# HalfBridge_V01.net
KiCad netlist of a schematic drawn in Altium Designer
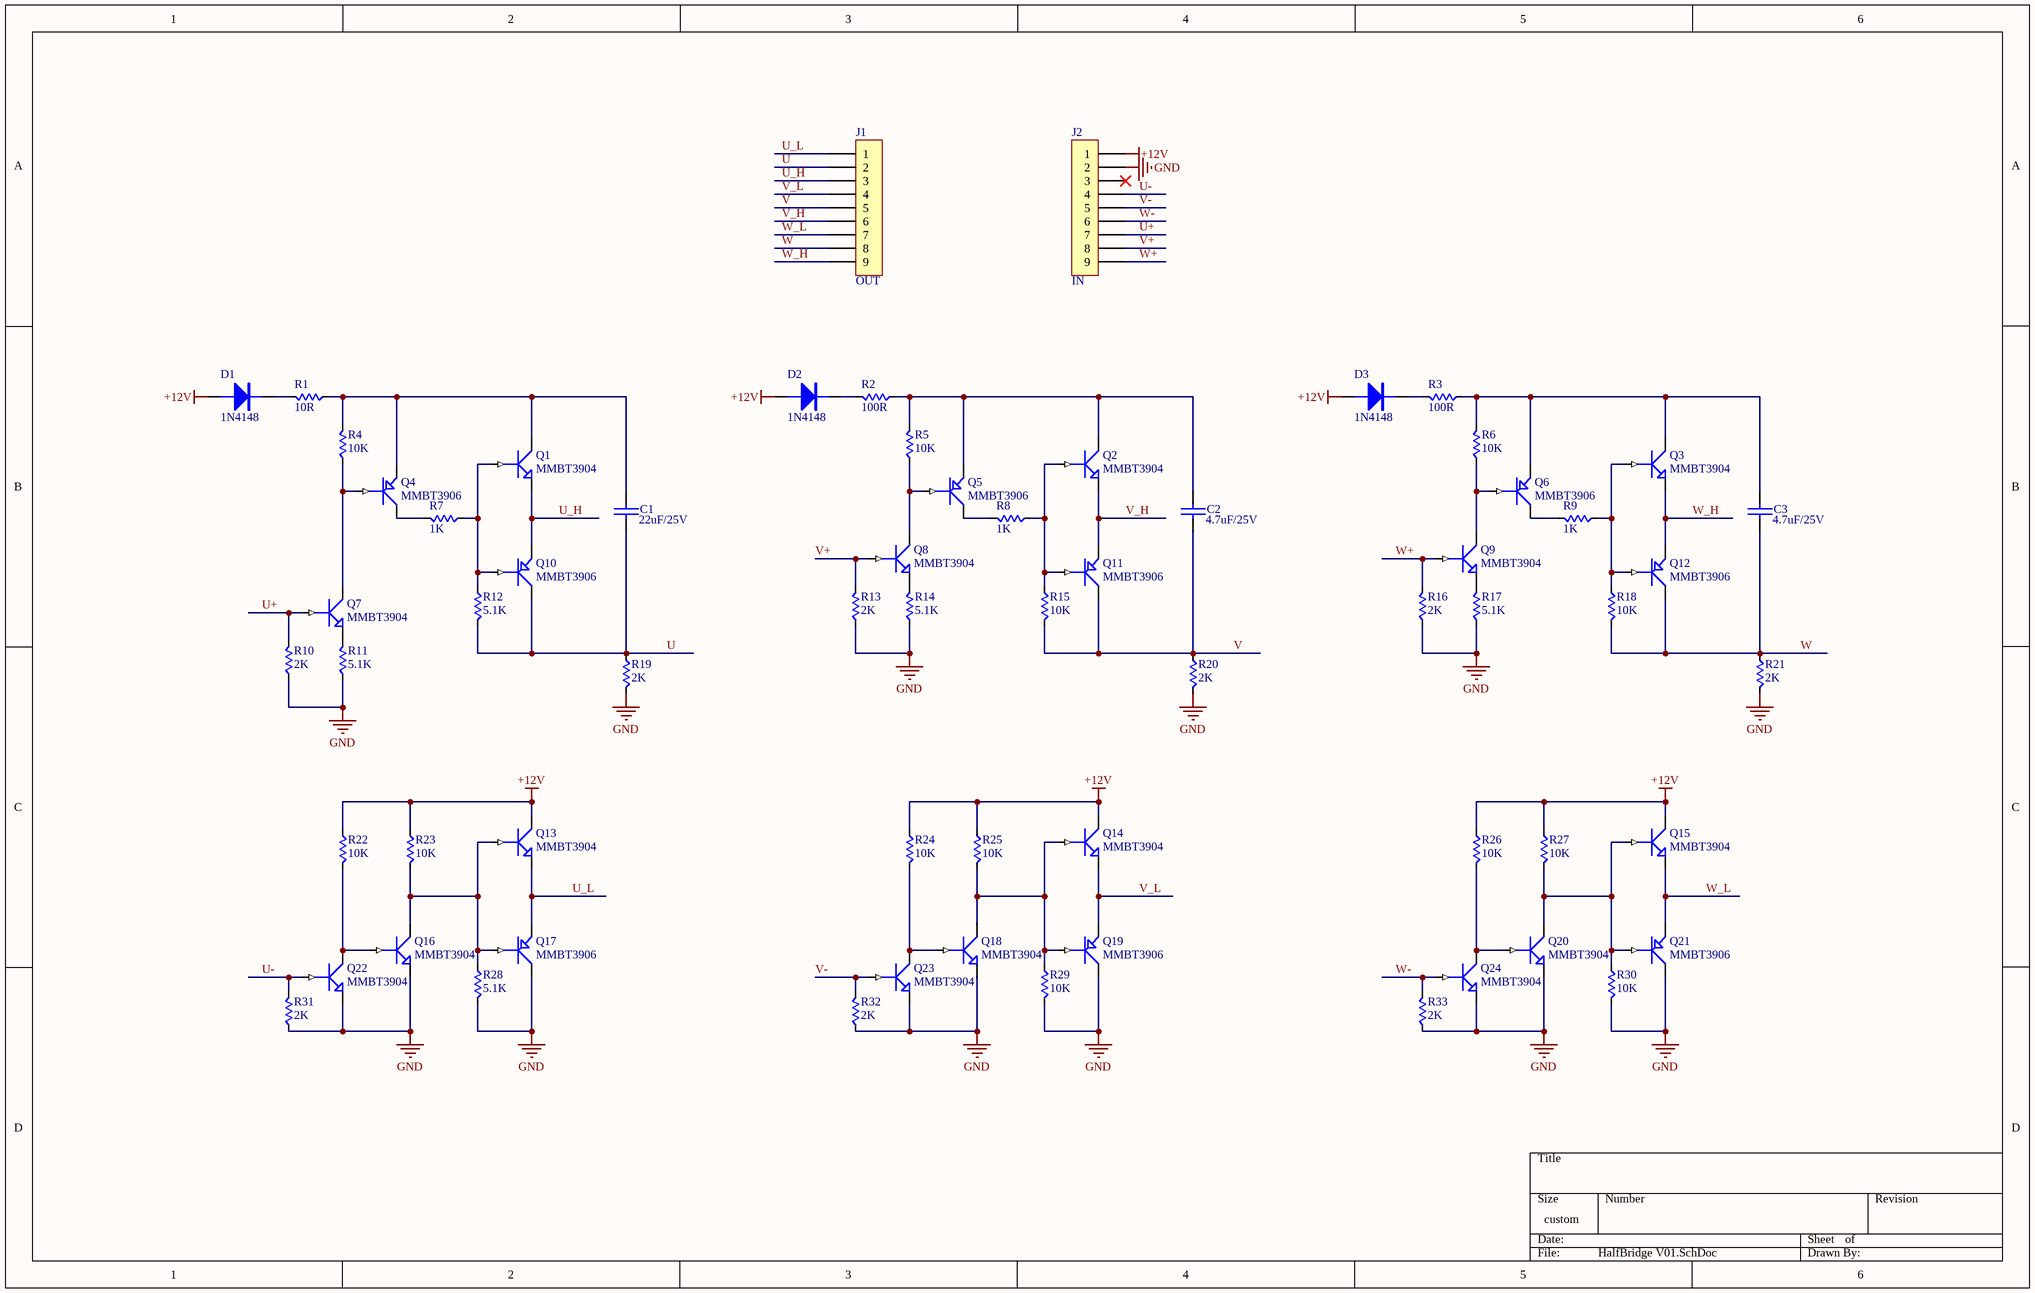
[diagram p0: HalfBridge V01.SchDoc]

(export (version "E")
  (design (tool "Eeschema 10.0.6"))
  (components
    (comp (ref "C1")
      (value "22uF/25V")
      (footprint "0805C")
      (description "Capacitor")
      (libsource (lib "*") (part "CAP"))
    )
    (comp (ref "C2")
      (value "4.7uF/25V")
      (footprint "0805C")
      (description "Capacitor")
      (libsource (lib "*") (part "CAP"))
    )
    (comp (ref "C3")
      (value "4.7uF/25V")
      (footprint "0805C")
      (description "Capacitor")
      (libsource (lib "*") (part "CAP"))
    )
    (comp (ref "D1")
      (value "1N4148")
      (footprint "SOD-123")
      (description "Diode")
      (libsource (lib "*") (part "DIODE1"))
    )
    (comp (ref "D2")
      (value "1N4148")
      (footprint "SOD-123")
      (description "Diode")
      (libsource (lib "*") (part "DIODE1"))
    )
    (comp (ref "D3")
      (value "1N4148")
      (footprint "SOD-123")
      (description "Diode")
      (libsource (lib "*") (part "DIODE1"))
    )
    (comp (ref "J1")
      (value "OUT")
      (footprint "SMT2.54-1X9-F")
      (description "Connector")
      (libsource (lib "") (part "CON9_1"))
    )
    (comp (ref "J2")
      (value "IN")
      (footprint "SMT2.54-1X9-F")
      (description "Connector")
      (libsource (lib "COFLY-SCH") (part "CON9"))
    )
    (comp (ref "Q1")
      (value "MMBT3904")
      (footprint "SOT-23S")
      (description "NPN Transistor")
      (libsource (lib "COFLY-SCH") (part "NPN1"))
    )
    (comp (ref "Q2")
      (value "MMBT3904")
      (footprint "SOT-23S")
      (description "NPN Transistor")
      (libsource (lib "COFLY-SCH") (part "NPN1"))
    )
    (comp (ref "Q3")
      (value "MMBT3904")
      (footprint "SOT-23S")
      (description "NPN Transistor")
      (libsource (lib "COFLY-SCH") (part "NPN1"))
    )
    (comp (ref "Q4")
      (value "MMBT3906")
      (footprint "SOT-23S")
      (description "PNP Transistor")
      (libsource (lib "COFLY-SCH") (part "PNP1"))
    )
    (comp (ref "Q5")
      (value "MMBT3906")
      (footprint "SOT-23S")
      (description "PNP Transistor")
      (libsource (lib "COFLY-SCH") (part "PNP1"))
    )
    (comp (ref "Q6")
      (value "MMBT3906")
      (footprint "SOT-23S")
      (description "PNP Transistor")
      (libsource (lib "COFLY-SCH") (part "PNP1"))
    )
    (comp (ref "Q7")
      (value "MMBT3904")
      (footprint "SOT-23S")
      (description "NPN Transistor")
      (libsource (lib "COFLY-SCH") (part "NPN1"))
    )
    (comp (ref "Q8")
      (value "MMBT3904")
      (footprint "SOT-23S")
      (description "NPN Transistor")
      (libsource (lib "COFLY-SCH") (part "NPN1"))
    )
    (comp (ref "Q9")
      (value "MMBT3904")
      (footprint "SOT-23S")
      (description "NPN Transistor")
      (libsource (lib "COFLY-SCH") (part "NPN1"))
    )
    (comp (ref "Q10")
      (value "MMBT3906")
      (footprint "SOT-23S")
      (description "PNP Transistor")
      (libsource (lib "COFLY-SCH") (part "PNP1"))
    )
    (comp (ref "Q11")
      (value "MMBT3906")
      (footprint "SOT-23S")
      (description "PNP Transistor")
      (libsource (lib "COFLY-SCH") (part "PNP1"))
    )
    (comp (ref "Q12")
      (value "MMBT3906")
      (footprint "SOT-23S")
      (description "PNP Transistor")
      (libsource (lib "COFLY-SCH") (part "PNP1"))
    )
    (comp (ref "Q13")
      (value "MMBT3904")
      (footprint "SOT-23S")
      (description "NPN Transistor")
      (libsource (lib "COFLY-SCH") (part "NPN1"))
    )
    (comp (ref "Q14")
      (value "MMBT3904")
      (footprint "SOT-23S")
      (description "NPN Transistor")
      (libsource (lib "COFLY-SCH") (part "NPN1"))
    )
    (comp (ref "Q15")
      (value "MMBT3904")
      (footprint "SOT-23S")
      (description "NPN Transistor")
      (libsource (lib "COFLY-SCH") (part "NPN1"))
    )
    (comp (ref "Q16")
      (value "MMBT3904")
      (footprint "SOT-23S")
      (description "NPN Transistor")
      (libsource (lib "COFLY-SCH") (part "NPN1"))
    )
    (comp (ref "Q17")
      (value "MMBT3906")
      (footprint "SOT-23S")
      (description "PNP Transistor")
      (libsource (lib "COFLY-SCH") (part "PNP1"))
    )
    (comp (ref "Q18")
      (value "MMBT3904")
      (footprint "SOT-23S")
      (description "NPN Transistor")
      (libsource (lib "COFLY-SCH") (part "NPN1"))
    )
    (comp (ref "Q19")
      (value "MMBT3906")
      (footprint "SOT-23S")
      (description "PNP Transistor")
      (libsource (lib "COFLY-SCH") (part "PNP1"))
    )
    (comp (ref "Q20")
      (value "MMBT3904")
      (footprint "SOT-23S")
      (description "NPN Transistor")
      (libsource (lib "COFLY-SCH") (part "NPN1"))
    )
    (comp (ref "Q21")
      (value "MMBT3906")
      (footprint "SOT-23S")
      (description "PNP Transistor")
      (libsource (lib "COFLY-SCH") (part "PNP1"))
    )
    (comp (ref "Q22")
      (value "MMBT3904")
      (footprint "SOT-23S")
      (description "NPN Transistor")
      (libsource (lib "COFLY-SCH") (part "NPN1"))
    )
    (comp (ref "Q23")
      (value "MMBT3904")
      (footprint "SOT-23S")
      (description "NPN Transistor")
      (libsource (lib "COFLY-SCH") (part "NPN1"))
    )
    (comp (ref "Q24")
      (value "MMBT3904")
      (footprint "SOT-23S")
      (description "NPN Transistor")
      (libsource (lib "COFLY-SCH") (part "NPN1"))
    )
    (comp (ref "R1") (value "10R") (footprint "0603R") (libsource (lib "COFLY-SCH") (part "RES")))
    (comp (ref "R2") (value "100R") (footprint "0603R") (libsource (lib "COFLY-SCH") (part "RES")))
    (comp (ref "R3") (value "100R") (footprint "0603R") (libsource (lib "COFLY-SCH") (part "RES")))
    (comp (ref "R4") (value "10K") (footprint "0603R") (libsource (lib "COFLY-SCH") (part "RES")))
    (comp (ref "R5") (value "10K") (footprint "0603R") (libsource (lib "COFLY-SCH") (part "RES")))
    (comp (ref "R6") (value "10K") (footprint "0603R") (libsource (lib "COFLY-SCH") (part "RES")))
    (comp (ref "R7") (value "1K") (footprint "0603R") (libsource (lib "COFLY-SCH") (part "RES")))
    (comp (ref "R8") (value "1K") (footprint "0603R") (libsource (lib "COFLY-SCH") (part "RES")))
    (comp (ref "R9") (value "1K") (footprint "0603R") (libsource (lib "COFLY-SCH") (part "RES")))
    (comp (ref "R10") (value "2K") (footprint "0603R") (libsource (lib "COFLY-SCH") (part "RES")))
    (comp (ref "R11") (value "5.1K") (footprint "0603R") (libsource (lib "COFLY-SCH") (part "RES")))
    (comp (ref "R12") (value "5.1K") (footprint "0603R") (libsource (lib "COFLY-SCH") (part "RES")))
    (comp (ref "R13") (value "2K") (footprint "0603R") (libsource (lib "COFLY-SCH") (part "RES")))
    (comp (ref "R14") (value "5.1K") (footprint "0603R") (libsource (lib "COFLY-SCH") (part "RES")))
    (comp (ref "R15") (value "10K") (footprint "0603R") (libsource (lib "COFLY-SCH") (part "RES")))
    (comp (ref "R16") (value "2K") (footprint "0603R") (libsource (lib "COFLY-SCH") (part "RES")))
    (comp (ref "R17") (value "5.1K") (footprint "0603R") (libsource (lib "COFLY-SCH") (part "RES")))
    (comp (ref "R18") (value "10K") (footprint "0603R") (libsource (lib "COFLY-SCH") (part "RES")))
    (comp (ref "R19") (value "2K") (footprint "0603R") (libsource (lib "COFLY-SCH") (part "RES")))
    (comp (ref "R20") (value "2K") (footprint "0603R") (libsource (lib "COFLY-SCH") (part "RES")))
    (comp (ref "R21") (value "2K") (footprint "0603R") (libsource (lib "COFLY-SCH") (part "RES")))
    (comp (ref "R22") (value "10K") (footprint "0603R") (libsource (lib "COFLY-SCH") (part "RES")))
    (comp (ref "R23") (value "10K") (footprint "0603R") (libsource (lib "COFLY-SCH") (part "RES")))
    (comp (ref "R24") (value "10K") (footprint "0603R") (libsource (lib "COFLY-SCH") (part "RES")))
    (comp (ref "R25") (value "10K") (footprint "0603R") (libsource (lib "COFLY-SCH") (part "RES")))
    (comp (ref "R26") (value "10K") (footprint "0603R") (libsource (lib "COFLY-SCH") (part "RES")))
    (comp (ref "R27") (value "10K") (footprint "0603R") (libsource (lib "COFLY-SCH") (part "RES")))
    (comp (ref "R28") (value "5.1K") (footprint "0603R") (libsource (lib "COFLY-SCH") (part "RES")))
    (comp (ref "R29") (value "10K") (footprint "0603R") (libsource (lib "COFLY-SCH") (part "RES")))
    (comp (ref "R30") (value "10K") (footprint "0603R") (libsource (lib "COFLY-SCH") (part "RES")))
    (comp (ref "R31") (value "2K") (footprint "0603R") (libsource (lib "COFLY-SCH") (part "RES")))
    (comp (ref "R32") (value "2K") (footprint "0603R") (libsource (lib "COFLY-SCH") (part "RES")))
    (comp (ref "R33") (value "2K") (footprint "0603R") (libsource (lib "COFLY-SCH") (part "RES")))
  )
  (nets
    (net (code "1") (name "+12V") (class "Default")
      (node (ref "D1") (pin "1") (pinfunction "1_1") (pintype "passive"))
      (node (ref "D2") (pin "1") (pinfunction "1_1") (pintype "passive"))
      (node (ref "D3") (pin "1") (pinfunction "1_1") (pintype "passive"))
      (node (ref "J2") (pin "1") (pinfunction "1_1") (pintype "passive"))
      (node (ref "Q13") (pin "3") (pinfunction "C_3") (pintype "passive"))
      (node (ref "Q14") (pin "3") (pinfunction "C_3") (pintype "passive"))
      (node (ref "Q15") (pin "3") (pinfunction "C_3") (pintype "passive"))
      (node (ref "R22") (pin "1") (pinfunction "1_1") (pintype "passive"))
      (node (ref "R23") (pin "1") (pinfunction "1_1") (pintype "passive"))
      (node (ref "R24") (pin "1") (pinfunction "1_1") (pintype "passive"))
      (node (ref "R25") (pin "1") (pinfunction "1_1") (pintype "passive"))
      (node (ref "R26") (pin "1") (pinfunction "1_1") (pintype "passive"))
      (node (ref "R27") (pin "1") (pinfunction "1_1") (pintype "passive"))
    )
    (net (code "2") (name "/U") (class "Default")
      (node (ref "C1") (pin "2") (pinfunction "2_2") (pintype "passive"))
      (node (ref "J1") (pin "2") (pinfunction "2_2") (pintype "passive"))
      (node (ref "Q10") (pin "3") (pinfunction "C_3") (pintype "passive"))
      (node (ref "R12") (pin "2") (pinfunction "2_2") (pintype "passive"))
      (node (ref "R19") (pin "2") (pinfunction "2_2") (pintype "passive"))
    )
    (net (code "3") (name "/U+") (class "Default")
      (node (ref "J2") (pin "7") (pinfunction "7_7") (pintype "passive"))
      (node (ref "Q7") (pin "1") (pinfunction "B_1") (pintype "input"))
      (node (ref "R10") (pin "2") (pinfunction "2_2") (pintype "passive"))
    )
    (net (code "4") (name "/U-") (class "Default")
      (node (ref "J2") (pin "4") (pinfunction "4_4") (pintype "passive"))
      (node (ref "Q22") (pin "1") (pinfunction "B_1") (pintype "input"))
      (node (ref "R31") (pin "2") (pinfunction "2_2") (pintype "passive"))
    )
    (net (code "5") (name "/U_H") (class "Default")
      (node (ref "J1") (pin "3") (pinfunction "3_3") (pintype "passive"))
      (node (ref "Q1") (pin "2") (pinfunction "E_2") (pintype "passive"))
      (node (ref "Q10") (pin "2") (pinfunction "E_2") (pintype "passive"))
    )
    (net (code "6") (name "/U_L") (class "Default")
      (node (ref "J1") (pin "1") (pinfunction "1_1") (pintype "passive"))
      (node (ref "Q13") (pin "2") (pinfunction "E_2") (pintype "passive"))
      (node (ref "Q17") (pin "2") (pinfunction "E_2") (pintype "passive"))
    )
    (net (code "7") (name "/V") (class "Default")
      (node (ref "C2") (pin "2") (pinfunction "2_2") (pintype "passive"))
      (node (ref "J1") (pin "5") (pinfunction "5_5") (pintype "passive"))
      (node (ref "Q11") (pin "3") (pinfunction "C_3") (pintype "passive"))
      (node (ref "R15") (pin "2") (pinfunction "2_2") (pintype "passive"))
      (node (ref "R20") (pin "2") (pinfunction "2_2") (pintype "passive"))
    )
    (net (code "8") (name "/V+") (class "Default")
      (node (ref "J2") (pin "8") (pinfunction "8_8") (pintype "passive"))
      (node (ref "Q8") (pin "1") (pinfunction "B_1") (pintype "input"))
      (node (ref "R13") (pin "2") (pinfunction "2_2") (pintype "passive"))
    )
    (net (code "9") (name "/V-") (class "Default")
      (node (ref "J2") (pin "5") (pinfunction "5_5") (pintype "passive"))
      (node (ref "Q23") (pin "1") (pinfunction "B_1") (pintype "input"))
      (node (ref "R32") (pin "2") (pinfunction "2_2") (pintype "passive"))
    )
    (net (code "10") (name "/V_H") (class "Default")
      (node (ref "J1") (pin "6") (pinfunction "6_6") (pintype "passive"))
      (node (ref "Q11") (pin "2") (pinfunction "E_2") (pintype "passive"))
      (node (ref "Q2") (pin "2") (pinfunction "E_2") (pintype "passive"))
    )
    (net (code "11") (name "/V_L") (class "Default")
      (node (ref "J1") (pin "4") (pinfunction "4_4") (pintype "passive"))
      (node (ref "Q14") (pin "2") (pinfunction "E_2") (pintype "passive"))
      (node (ref "Q19") (pin "2") (pinfunction "E_2") (pintype "passive"))
    )
    (net (code "12") (name "/W") (class "Default")
      (node (ref "C3") (pin "2") (pinfunction "2_2") (pintype "passive"))
      (node (ref "J1") (pin "8") (pinfunction "8_8") (pintype "passive"))
      (node (ref "Q12") (pin "3") (pinfunction "C_3") (pintype "passive"))
      (node (ref "R18") (pin "2") (pinfunction "2_2") (pintype "passive"))
      (node (ref "R21") (pin "2") (pinfunction "2_2") (pintype "passive"))
    )
    (net (code "13") (name "/W+") (class "Default")
      (node (ref "J2") (pin "9") (pinfunction "9_9") (pintype "passive"))
      (node (ref "Q9") (pin "1") (pinfunction "B_1") (pintype "input"))
      (node (ref "R16") (pin "2") (pinfunction "2_2") (pintype "passive"))
    )
    (net (code "14") (name "/W-") (class "Default")
      (node (ref "J2") (pin "6") (pinfunction "6_6") (pintype "passive"))
      (node (ref "Q24") (pin "1") (pinfunction "B_1") (pintype "input"))
      (node (ref "R33") (pin "2") (pinfunction "2_2") (pintype "passive"))
    )
    (net (code "15") (name "/W_H") (class "Default")
      (node (ref "J1") (pin "9") (pinfunction "9_9") (pintype "passive"))
      (node (ref "Q12") (pin "2") (pinfunction "E_2") (pintype "passive"))
      (node (ref "Q3") (pin "2") (pinfunction "E_2") (pintype "passive"))
    )
    (net (code "16") (name "/W_L") (class "Default")
      (node (ref "J1") (pin "7") (pinfunction "7_7") (pintype "passive"))
      (node (ref "Q15") (pin "2") (pinfunction "E_2") (pintype "passive"))
      (node (ref "Q21") (pin "2") (pinfunction "E_2") (pintype "passive"))
    )
    (net (code "17") (name "GND") (class "Default")
      (node (ref "J2") (pin "2") (pinfunction "2_2") (pintype "passive"))
      (node (ref "Q16") (pin "2") (pinfunction "E_2") (pintype "passive"))
      (node (ref "Q17") (pin "3") (pinfunction "C_3") (pintype "passive"))
      (node (ref "Q18") (pin "2") (pinfunction "E_2") (pintype "passive"))
      (node (ref "Q19") (pin "3") (pinfunction "C_3") (pintype "passive"))
      (node (ref "Q20") (pin "2") (pinfunction "E_2") (pintype "passive"))
      (node (ref "Q21") (pin "3") (pinfunction "C_3") (pintype "passive"))
      (node (ref "Q22") (pin "2") (pinfunction "E_2") (pintype "passive"))
      (node (ref "Q23") (pin "2") (pinfunction "E_2") (pintype "passive"))
      (node (ref "Q24") (pin "2") (pinfunction "E_2") (pintype "passive"))
      (node (ref "R10") (pin "1") (pinfunction "1_1") (pintype "passive"))
      (node (ref "R11") (pin "1") (pinfunction "1_1") (pintype "passive"))
      (node (ref "R13") (pin "1") (pinfunction "1_1") (pintype "passive"))
      (node (ref "R14") (pin "1") (pinfunction "1_1") (pintype "passive"))
      (node (ref "R16") (pin "1") (pinfunction "1_1") (pintype "passive"))
      (node (ref "R17") (pin "1") (pinfunction "1_1") (pintype "passive"))
      (node (ref "R19") (pin "1") (pinfunction "1_1") (pintype "passive"))
      (node (ref "R20") (pin "1") (pinfunction "1_1") (pintype "passive"))
      (node (ref "R21") (pin "1") (pinfunction "1_1") (pintype "passive"))
      (node (ref "R28") (pin "2") (pinfunction "2_2") (pintype "passive"))
      (node (ref "R29") (pin "2") (pinfunction "2_2") (pintype "passive"))
      (node (ref "R30") (pin "2") (pinfunction "2_2") (pintype "passive"))
      (node (ref "R31") (pin "1") (pinfunction "1_1") (pintype "passive"))
      (node (ref "R32") (pin "1") (pinfunction "1_1") (pintype "passive"))
      (node (ref "R33") (pin "1") (pinfunction "1_1") (pintype "passive"))
    )
    (net (code "18") (name "Net-(D1-Pad2)") (class "Default")
      (node (ref "D1") (pin "2") (pinfunction "2_2") (pintype "passive"))
      (node (ref "R1") (pin "2") (pinfunction "2_2") (pintype "passive"))
    )
    (net (code "19") (name "Net-(D2-Pad2)") (class "Default")
      (node (ref "D2") (pin "2") (pinfunction "2_2") (pintype "passive"))
      (node (ref "R2") (pin "2") (pinfunction "2_2") (pintype "passive"))
    )
    (net (code "20") (name "Net-(D3-Pad2)") (class "Default")
      (node (ref "D3") (pin "2") (pinfunction "2_2") (pintype "passive"))
      (node (ref "R3") (pin "2") (pinfunction "2_2") (pintype "passive"))
    )
    (net (code "21") (name "Net-(Q1-B)") (class "Default")
      (node (ref "Q1") (pin "1") (pinfunction "B_1") (pintype "input"))
      (node (ref "Q10") (pin "1") (pinfunction "B_1") (pintype "input"))
      (node (ref "R12") (pin "1") (pinfunction "1_1") (pintype "passive"))
      (node (ref "R7") (pin "1") (pinfunction "1_1") (pintype "passive"))
    )
    (net (code "22") (name "Net-(Q1-C)") (class "Default")
      (node (ref "C1") (pin "1") (pinfunction "1_1") (pintype "passive"))
      (node (ref "Q1") (pin "3") (pinfunction "C_3") (pintype "passive"))
      (node (ref "Q4") (pin "2") (pinfunction "E_2") (pintype "passive"))
      (node (ref "R1") (pin "1") (pinfunction "1_1") (pintype "passive"))
      (node (ref "R4") (pin "2") (pinfunction "2_2") (pintype "passive"))
    )
    (net (code "23") (name "Net-(Q2-C)") (class "Default")
      (node (ref "C2") (pin "1") (pinfunction "1_1") (pintype "passive"))
      (node (ref "Q2") (pin "3") (pinfunction "C_3") (pintype "passive"))
      (node (ref "Q5") (pin "2") (pinfunction "E_2") (pintype "passive"))
      (node (ref "R2") (pin "1") (pinfunction "1_1") (pintype "passive"))
      (node (ref "R5") (pin "2") (pinfunction "2_2") (pintype "passive"))
    )
    (net (code "24") (name "Net-(Q3-C)") (class "Default")
      (node (ref "C3") (pin "1") (pinfunction "1_1") (pintype "passive"))
      (node (ref "Q3") (pin "3") (pinfunction "C_3") (pintype "passive"))
      (node (ref "Q6") (pin "2") (pinfunction "E_2") (pintype "passive"))
      (node (ref "R3") (pin "1") (pinfunction "1_1") (pintype "passive"))
      (node (ref "R6") (pin "2") (pinfunction "2_2") (pintype "passive"))
    )
    (net (code "25") (name "Net-(Q4-B)") (class "Default")
      (node (ref "Q4") (pin "1") (pinfunction "B_1") (pintype "input"))
      (node (ref "Q7") (pin "3") (pinfunction "C_3") (pintype "passive"))
      (node (ref "R4") (pin "1") (pinfunction "1_1") (pintype "passive"))
    )
    (net (code "26") (name "Net-(Q4-C)") (class "Default")
      (node (ref "Q4") (pin "3") (pinfunction "C_3") (pintype "passive"))
      (node (ref "R7") (pin "2") (pinfunction "2_2") (pintype "passive"))
    )
    (net (code "27") (name "Net-(Q5-B)") (class "Default")
      (node (ref "Q5") (pin "1") (pinfunction "B_1") (pintype "input"))
      (node (ref "Q8") (pin "3") (pinfunction "C_3") (pintype "passive"))
      (node (ref "R5") (pin "1") (pinfunction "1_1") (pintype "passive"))
    )
    (net (code "28") (name "Net-(Q5-C)") (class "Default")
      (node (ref "Q5") (pin "3") (pinfunction "C_3") (pintype "passive"))
      (node (ref "R8") (pin "2") (pinfunction "2_2") (pintype "passive"))
    )
    (net (code "29") (name "Net-(Q6-B)") (class "Default")
      (node (ref "Q6") (pin "1") (pinfunction "B_1") (pintype "input"))
      (node (ref "Q9") (pin "3") (pinfunction "C_3") (pintype "passive"))
      (node (ref "R6") (pin "1") (pinfunction "1_1") (pintype "passive"))
    )
    (net (code "30") (name "Net-(Q6-C)") (class "Default")
      (node (ref "Q6") (pin "3") (pinfunction "C_3") (pintype "passive"))
      (node (ref "R9") (pin "2") (pinfunction "2_2") (pintype "passive"))
    )
    (net (code "31") (name "Net-(Q7-E)") (class "Default")
      (node (ref "Q7") (pin "2") (pinfunction "E_2") (pintype "passive"))
      (node (ref "R11") (pin "2") (pinfunction "2_2") (pintype "passive"))
    )
    (net (code "32") (name "Net-(Q8-E)") (class "Default")
      (node (ref "Q8") (pin "2") (pinfunction "E_2") (pintype "passive"))
      (node (ref "R14") (pin "2") (pinfunction "2_2") (pintype "passive"))
    )
    (net (code "33") (name "Net-(Q9-E)") (class "Default")
      (node (ref "Q9") (pin "2") (pinfunction "E_2") (pintype "passive"))
      (node (ref "R17") (pin "2") (pinfunction "2_2") (pintype "passive"))
    )
    (net (code "34") (name "Net-(Q11-B)") (class "Default")
      (node (ref "Q11") (pin "1") (pinfunction "B_1") (pintype "input"))
      (node (ref "Q2") (pin "1") (pinfunction "B_1") (pintype "input"))
      (node (ref "R15") (pin "1") (pinfunction "1_1") (pintype "passive"))
      (node (ref "R8") (pin "1") (pinfunction "1_1") (pintype "passive"))
    )
    (net (code "35") (name "Net-(Q12-B)") (class "Default")
      (node (ref "Q12") (pin "1") (pinfunction "B_1") (pintype "input"))
      (node (ref "Q3") (pin "1") (pinfunction "B_1") (pintype "input"))
      (node (ref "R18") (pin "1") (pinfunction "1_1") (pintype "passive"))
      (node (ref "R9") (pin "1") (pinfunction "1_1") (pintype "passive"))
    )
    (net (code "36") (name "Net-(Q13-B)") (class "Default")
      (node (ref "Q13") (pin "1") (pinfunction "B_1") (pintype "input"))
      (node (ref "Q16") (pin "3") (pinfunction "C_3") (pintype "passive"))
      (node (ref "Q17") (pin "1") (pinfunction "B_1") (pintype "input"))
      (node (ref "R23") (pin "2") (pinfunction "2_2") (pintype "passive"))
      (node (ref "R28") (pin "1") (pinfunction "1_1") (pintype "passive"))
    )
    (net (code "37") (name "Net-(Q14-B)") (class "Default")
      (node (ref "Q14") (pin "1") (pinfunction "B_1") (pintype "input"))
      (node (ref "Q18") (pin "3") (pinfunction "C_3") (pintype "passive"))
      (node (ref "Q19") (pin "1") (pinfunction "B_1") (pintype "input"))
      (node (ref "R25") (pin "2") (pinfunction "2_2") (pintype "passive"))
      (node (ref "R29") (pin "1") (pinfunction "1_1") (pintype "passive"))
    )
    (net (code "38") (name "Net-(Q15-B)") (class "Default")
      (node (ref "Q15") (pin "1") (pinfunction "B_1") (pintype "input"))
      (node (ref "Q20") (pin "3") (pinfunction "C_3") (pintype "passive"))
      (node (ref "Q21") (pin "1") (pinfunction "B_1") (pintype "input"))
      (node (ref "R27") (pin "2") (pinfunction "2_2") (pintype "passive"))
      (node (ref "R30") (pin "1") (pinfunction "1_1") (pintype "passive"))
    )
    (net (code "39") (name "Net-(Q16-B)") (class "Default")
      (node (ref "Q16") (pin "1") (pinfunction "B_1") (pintype "input"))
      (node (ref "Q22") (pin "3") (pinfunction "C_3") (pintype "passive"))
      (node (ref "R22") (pin "2") (pinfunction "2_2") (pintype "passive"))
    )
    (net (code "40") (name "Net-(Q18-B)") (class "Default")
      (node (ref "Q18") (pin "1") (pinfunction "B_1") (pintype "input"))
      (node (ref "Q23") (pin "3") (pinfunction "C_3") (pintype "passive"))
      (node (ref "R24") (pin "2") (pinfunction "2_2") (pintype "passive"))
    )
    (net (code "41") (name "Net-(Q20-B)") (class "Default")
      (node (ref "Q20") (pin "1") (pinfunction "B_1") (pintype "input"))
      (node (ref "Q24") (pin "3") (pinfunction "C_3") (pintype "passive"))
      (node (ref "R26") (pin "2") (pinfunction "2_2") (pintype "passive"))
    )
    (net (code "42") (name "unconnected-(J2-Pad3)") (class "Default")
      (node (ref "J2") (pin "3") (pinfunction "3_3") (pintype "passive+no_connect"))
    )
  )
)
